# Sheet_Hearth.net
KiCad netlist of a schematic drawn in Altium Designer
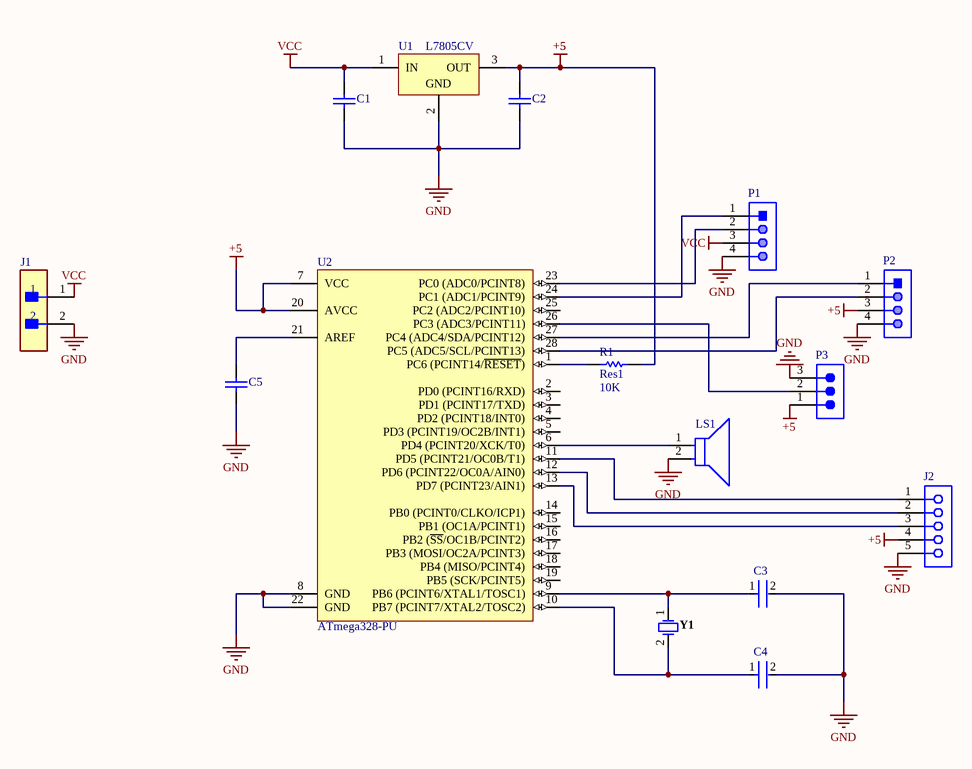
[diagram p0: Sheet_Hearth.SchDoc]

(export (version "E")
  (design (tool "Eeschema 10.0.6"))
  (components
    (comp (ref "C1")
      (value "K104K15X7RF5TL2")
      (footprint "VISH-K104K15X7RF5TL2")
      (description "Ceramic Capacitor, 100 nF, +/- 10%, 50 V, -55 to 125 degC, 2-Pin THD, RoHS, Tape and Reel")
      (fields (field (name "MANUFACTURER") "Vishay") (field (name "TOLERANCE") "±10%"))
      (libsource (lib "Altium Content Vault") (part "CAP-NP-2"))
    )
    (comp (ref "C2")
      (value "K104K15X7RF5TL2")
      (footprint "VISH-K104K15X7RF5TL2")
      (description "Ceramic Capacitor, 100 nF, +/- 10%, 50 V, -55 to 125 degC, 2-Pin THD, RoHS, Tape and Reel")
      (fields (field (name "MANUFACTURER") "Vishay") (field (name "TOLERANCE") "±10%"))
      (libsource (lib "Altium Content Vault") (part "CAP-NP-2"))
    )
    (comp (ref "C3")
      (value "RCE5C1H220J0DBH03A")
      (footprint "FP-RCE0DB-MFG")
      (description "Cap Ceramic 22pF 50V C0G ±5% Radial 2.5mm +125°C Ammo Pack")
      (fields (field (name "TOLERANCE") "5%"))
      (libsource (lib "Altium Content Vault") (part "b4654b650e69147ec39a6b967a45e02"))
    )
    (comp (ref "C4")
      (value "RCE5C1H220J0DBH03A")
      (footprint "FP-RCE0DB-MFG")
      (description "Cap Ceramic 22pF 50V C0G ±5% Radial 2.5mm +125°C Ammo Pack")
      (fields (field (name "TOLERANCE") "5%"))
      (libsource (lib "Altium Content Vault") (part "b4654b650e69147ec39a6b967a45e02"))
    )
    (comp (ref "C5")
      (value "K104K15X7RF5TL2")
      (footprint "VISH-K104K15X7RF5TL2")
      (description "Ceramic Capacitor, 100 nF, +/- 10%, 50 V, -55 to 125 degC, 2-Pin THD, RoHS, Tape and Reel")
      (fields (field (name "MANUFACTURER") "Vishay") (field (name "TOLERANCE") "±10%"))
      (libsource (lib "Altium Content Vault") (part "CAP-NP-2"))
    )
    (comp (ref "J1")
      (value "TSW-102-07-L-S")
      (footprint "FP-TSW-102-07-L-S-MFG")
      (description "CONN HEADER VERT 2POS 2.54MM")
      (libsource (lib "Altium Content Vault") (part "3bc925449376181038e59eaffc5286c"))
    )
    (comp (ref "J2")
      (value "SSQ-105-02-L-S-RA")
      (footprint "SMTC-SSQ-105-02-X-S-RA")
      (description "SQ Post Socket, Through-hole, Right Angle, -55 to 125 degC, 2.54 mm Pitch, 5-Pin, Female, RoHS")
      (fields (field (name "MANUFACTURER") "Samtec"))
      (libsource (lib "Altium Content Vault") (part "SMTC-SSQ-105-02-X-S-RA"))
    )
    (comp (ref "LS1")
      (value "SD1209T5-A1")
      (footprint "FP-SD1209-MFG")
      (description "AUDIO MAGNETIC XDCR 3-6V TH")
      (libsource (lib "Altium Content Vault") (part "1973c4b650225fd2ddacaff6b763965"))
    )
    (comp (ref "P1")
      (value "61300411021")
      (footprint "61300411021")
      (description "THT Angled Pin Header WR-PHD, Pitch 2.54 mm, Single Row, 4 pins")
      (fields (field (name "MANUFACTURER") "Wurth Elektronik") (field (name "PUBLISHER") "WurthElektronik"))
      (libsource (lib "Altium Content Vault") (part "WE-CN-1P-M-R4"))
    )
    (comp (ref "P2")
      (value "61300411021")
      (footprint "61300411021")
      (description "THT Angled Pin Header WR-PHD, Pitch 2.54 mm, Single Row, 4 pins")
      (fields (field (name "MANUFACTURER") "Wurth Elektronik") (field (name "PUBLISHER") "WurthElektronik"))
      (libsource (lib "Altium Content Vault") (part "WE-CN-1P-M-R4"))
    )
    (comp (ref "P3")
      (value "MTSW-103-08-L-S-229-RA")
      (footprint "SMTC-MTSW-103-08-X-S-229-RA")
      (fields (field (name "MANUFACTURER") "Samtec"))
      (libsource (lib "Altium Content Vault") (part "SMTC-MTSW-103-08-X-S-229-RA"))
    )
    (comp (ref "R1")
      (value "Res1")
      (footprint "AXIAL-0.3")
      (description "Resistor")
      (fields (field (name "ALTIUM_VALUE") "10K") (field (name "PUBLISHER") "Altium Limited"))
      (libsource (lib "Miscellaneous Devices") (part "Res1"))
    )
    (comp (ref "U1")
      (value "L7805CV")
      (footprint "TO220")
      (description "Positive Voltage Regulator, 5V, 3-Pin TO-220")
      (libsource (lib "Altium Content Vault") (part "PM-REG-L4940-SIL3"))
    )
    (comp (ref "U2")
      (value "ATmega328-PU")
      (footprint "28P3")
      (libsource (lib "Altium Content Vault") (part "MC-8B-ATM48-IL28"))
    )
    (comp (ref "Y1")
      (value "FOXSLF/160-20")
      (footprint "FOX-FOXSLF160-20")
      (description "Resistance Weld Thru-Hole Crystal, 16 MHz, -20 to 70 degC, 2-Pin THD, RoHS, Bulk")
      (fields (field (name "TOLERANCE") "1%"))
      (libsource (lib "Altium Content Vault") (part "XTAL-1-2-2"))
    )
  )
  (nets
    (net (code "1") (name "+5") (class "Default")
      (node (ref "C2") (pin "2") (pinfunction "2_2") (pintype "passive"))
      (node (ref "J2") (pin "4") (pinfunction "4_4") (pintype "passive"))
      (node (ref "P2") (pin "3") (pinfunction "3_3") (pintype "passive"))
      (node (ref "P3") (pin "1") (pinfunction "1_1") (pintype "passive"))
      (node (ref "R1") (pin "2") (pinfunction "2_2") (pintype "passive"))
      (node (ref "U1") (pin "3") (pinfunction "OUT_3") (pintype "power_in"))
      (node (ref "U2") (pin "20") (pinfunction "AVCC_20") (pintype "power_in"))
      (node (ref "U2") (pin "7") (pinfunction "VCC_7") (pintype "power_in"))
    )
    (net (code "2") (name "GND") (class "Default")
      (node (ref "C1") (pin "2") (pinfunction "2_2") (pintype "passive"))
      (node (ref "C2") (pin "1") (pinfunction "1_1") (pintype "passive"))
      (node (ref "C3") (pin "2") (pinfunction "2_2") (pintype "passive"))
      (node (ref "C4") (pin "2") (pinfunction "2_2") (pintype "passive"))
      (node (ref "C5") (pin "1") (pinfunction "1_1") (pintype "passive"))
      (node (ref "J1") (pin "2") (pinfunction "2_2") (pintype "passive"))
      (node (ref "J2") (pin "5") (pinfunction "5_5") (pintype "passive"))
      (node (ref "LS1") (pin "2") (pinfunction "A_2") (pintype "passive"))
      (node (ref "P1") (pin "4") (pinfunction "4_4") (pintype "passive"))
      (node (ref "P2") (pin "4") (pinfunction "4_4") (pintype "passive"))
      (node (ref "P3") (pin "3") (pinfunction "3_3") (pintype "passive"))
      (node (ref "U1") (pin "2") (pinfunction "GND_2") (pintype "power_in"))
      (node (ref "U2") (pin "22") (pinfunction "GND_22") (pintype "power_in"))
      (node (ref "U2") (pin "8") (pinfunction "GND_8") (pintype "power_in"))
    )
    (net (code "3") (name "Net-(LS1-C)") (class "Default")
      (node (ref "LS1") (pin "1") (pinfunction "C_1") (pintype "passive"))
      (node (ref "U2") (pin "6") (pinfunction "PD4_(PCINT20/XCK/T0)_6") (pintype "bidirectional"))
    )
    (net (code "4") (name "Net-(U2-AREF)") (class "Default")
      (node (ref "C5") (pin "2") (pinfunction "2_2") (pintype "passive"))
      (node (ref "U2") (pin "21") (pinfunction "AREF_21") (pintype "power_in"))
    )
    (net (code "5") (name "Net-(U2-PB6_(PCINT6{slash}XTAL1{slash}TOSC1))") (class "Default")
      (node (ref "C3") (pin "1") (pinfunction "1_1") (pintype "passive"))
      (node (ref "U2") (pin "9") (pinfunction "PB6_(PCINT6/XTAL1/TOSC1)_9") (pintype "bidirectional"))
      (node (ref "Y1") (pin "1") (pinfunction "1_1") (pintype "passive"))
    )
    (net (code "6") (name "Net-(U2-PB7_(PCINT7{slash}XTAL2{slash}TOSC2))") (class "Default")
      (node (ref "C4") (pin "1") (pinfunction "1_1") (pintype "passive"))
      (node (ref "U2") (pin "10") (pinfunction "PB7_(PCINT7/XTAL2/TOSC2)_10") (pintype "bidirectional"))
      (node (ref "Y1") (pin "2") (pinfunction "2_2") (pintype "passive"))
    )
    (net (code "7") (name "Net-(U2-PC0_(ADC0{slash}PCINT8))") (class "Default")
      (node (ref "P1") (pin "2") (pinfunction "2_2") (pintype "passive"))
      (node (ref "U2") (pin "23") (pinfunction "PC0_(ADC0/PCINT8)_23") (pintype "bidirectional"))
    )
    (net (code "8") (name "Net-(U2-PC1_(ADC1{slash}PCINT9))") (class "Default")
      (node (ref "P1") (pin "1") (pinfunction "1_1") (pintype "passive"))
      (node (ref "U2") (pin "24") (pinfunction "PC1_(ADC1/PCINT9)_24") (pintype "bidirectional"))
    )
    (net (code "9") (name "Net-(U2-PC3_(ADC3{slash}PCINT11))") (class "Default")
      (node (ref "P3") (pin "2") (pinfunction "2_2") (pintype "passive"))
      (node (ref "U2") (pin "26") (pinfunction "PC3_(ADC3/PCINT11)_26") (pintype "bidirectional"))
    )
    (net (code "10") (name "Net-(U2-PC4_(ADC4{slash}SDA{slash}PCINT12))") (class "Default")
      (node (ref "P2") (pin "1") (pinfunction "1_1") (pintype "passive"))
      (node (ref "U2") (pin "27") (pinfunction "PC4_(ADC4/SDA/PCINT12)_27") (pintype "bidirectional"))
    )
    (net (code "11") (name "Net-(U2-PC5_(ADC5{slash}SCL{slash}PCINT13))") (class "Default")
      (node (ref "P2") (pin "2") (pinfunction "2_2") (pintype "passive"))
      (node (ref "U2") (pin "28") (pinfunction "PC5_(ADC5/SCL/PCINT13)_28") (pintype "bidirectional"))
    )
    (net (code "12") (name "Net-(U2-PC6_(PCINT14{slash}~{RESET}))") (class "Default")
      (node (ref "R1") (pin "1") (pinfunction "1_1") (pintype "passive"))
      (node (ref "U2") (pin "1") (pinfunction "PC6_(PCINT14/~{RESET})_1") (pintype "bidirectional"))
    )
    (net (code "13") (name "Net-(U2-PD5_(PCINT21{slash}OC0B{slash}T1))") (class "Default")
      (node (ref "J2") (pin "1") (pinfunction "1_1") (pintype "passive"))
      (node (ref "U2") (pin "11") (pinfunction "PD5_(PCINT21/OC0B/T1)_11") (pintype "bidirectional"))
    )
    (net (code "14") (name "Net-(U2-PD6_(PCINT22{slash}OC0A{slash}AIN0))") (class "Default")
      (node (ref "J2") (pin "2") (pinfunction "2_2") (pintype "passive"))
      (node (ref "U2") (pin "12") (pinfunction "PD6_(PCINT22/OC0A/AIN0)_12") (pintype "bidirectional"))
    )
    (net (code "15") (name "Net-(U2-PD7_(PCINT23{slash}AIN1))") (class "Default")
      (node (ref "J2") (pin "3") (pinfunction "3_3") (pintype "passive"))
      (node (ref "U2") (pin "13") (pinfunction "PD7_(PCINT23/AIN1)_13") (pintype "bidirectional"))
    )
    (net (code "16") (name "VCC") (class "Default")
      (node (ref "C1") (pin "1") (pinfunction "1_1") (pintype "passive"))
      (node (ref "J1") (pin "1") (pinfunction "1_1") (pintype "passive"))
      (node (ref "P1") (pin "3") (pinfunction "3_3") (pintype "passive"))
      (node (ref "U1") (pin "1") (pinfunction "IN_1") (pintype "power_in"))
    )
    (net (code "17") (name "unconnected-(U2-PB0_(PCINT0{slash}CLKO{slash}ICP1)-Pad14)") (class "Default")
      (node (ref "U2") (pin "14") (pinfunction "PB0_(PCINT0/CLKO/ICP1)_14") (pintype "bidirectional"))
    )
    (net (code "18") (name "unconnected-(U2-PB1_(OC1A{slash}PCINT1)-Pad15)") (class "Default")
      (node (ref "U2") (pin "15") (pinfunction "PB1_(OC1A/PCINT1)_15") (pintype "bidirectional"))
    )
    (net (code "19") (name "unconnected-(U2-PB2_(~{SS}{slash}OC1B{slash}PCINT2)-Pad16)") (class "Default")
      (node (ref "U2") (pin "16") (pinfunction "PB2_(~{SS}/OC1B/PCINT2)_16") (pintype "bidirectional"))
    )
    (net (code "20") (name "unconnected-(U2-PB3_(MOSI{slash}OC2A{slash}PCINT3)-Pad17)") (class "Default")
      (node (ref "U2") (pin "17") (pinfunction "PB3_(MOSI/OC2A/PCINT3)_17") (pintype "bidirectional"))
    )
    (net (code "21") (name "unconnected-(U2-PB4_(MISO{slash}PCINT4)-Pad18)") (class "Default")
      (node (ref "U2") (pin "18") (pinfunction "PB4_(MISO/PCINT4)_18") (pintype "bidirectional"))
    )
    (net (code "22") (name "unconnected-(U2-PB5_(SCK{slash}PCINT5)-Pad19)") (class "Default")
      (node (ref "U2") (pin "19") (pinfunction "PB5_(SCK/PCINT5)_19") (pintype "bidirectional"))
    )
    (net (code "23") (name "unconnected-(U2-PC2_(ADC2{slash}PCINT10)-Pad25)") (class "Default")
      (node (ref "U2") (pin "25") (pinfunction "PC2_(ADC2/PCINT10)_25") (pintype "bidirectional"))
    )
    (net (code "24") (name "unconnected-(U2-PD0_(PCINT16{slash}RXD)-Pad2)") (class "Default")
      (node (ref "U2") (pin "2") (pinfunction "PD0_(PCINT16/RXD)_2") (pintype "bidirectional"))
    )
    (net (code "25") (name "unconnected-(U2-PD1_(PCINT17{slash}TXD)-Pad3)") (class "Default")
      (node (ref "U2") (pin "3") (pinfunction "PD1_(PCINT17/TXD)_3") (pintype "bidirectional"))
    )
    (net (code "26") (name "unconnected-(U2-PD2_(PCINT18{slash}INT0)-Pad4)") (class "Default")
      (node (ref "U2") (pin "4") (pinfunction "PD2_(PCINT18/INT0)_4") (pintype "bidirectional"))
    )
    (net (code "27") (name "unconnected-(U2-PD3_(PCINT19{slash}OC2B{slash}INT1)-Pad5)") (class "Default")
      (node (ref "U2") (pin "5") (pinfunction "PD3_(PCINT19/OC2B/INT1)_5") (pintype "bidirectional"))
    )
  )
)
